# foe-scale.net
KiCad netlist of a schematic drawn in EAGLE
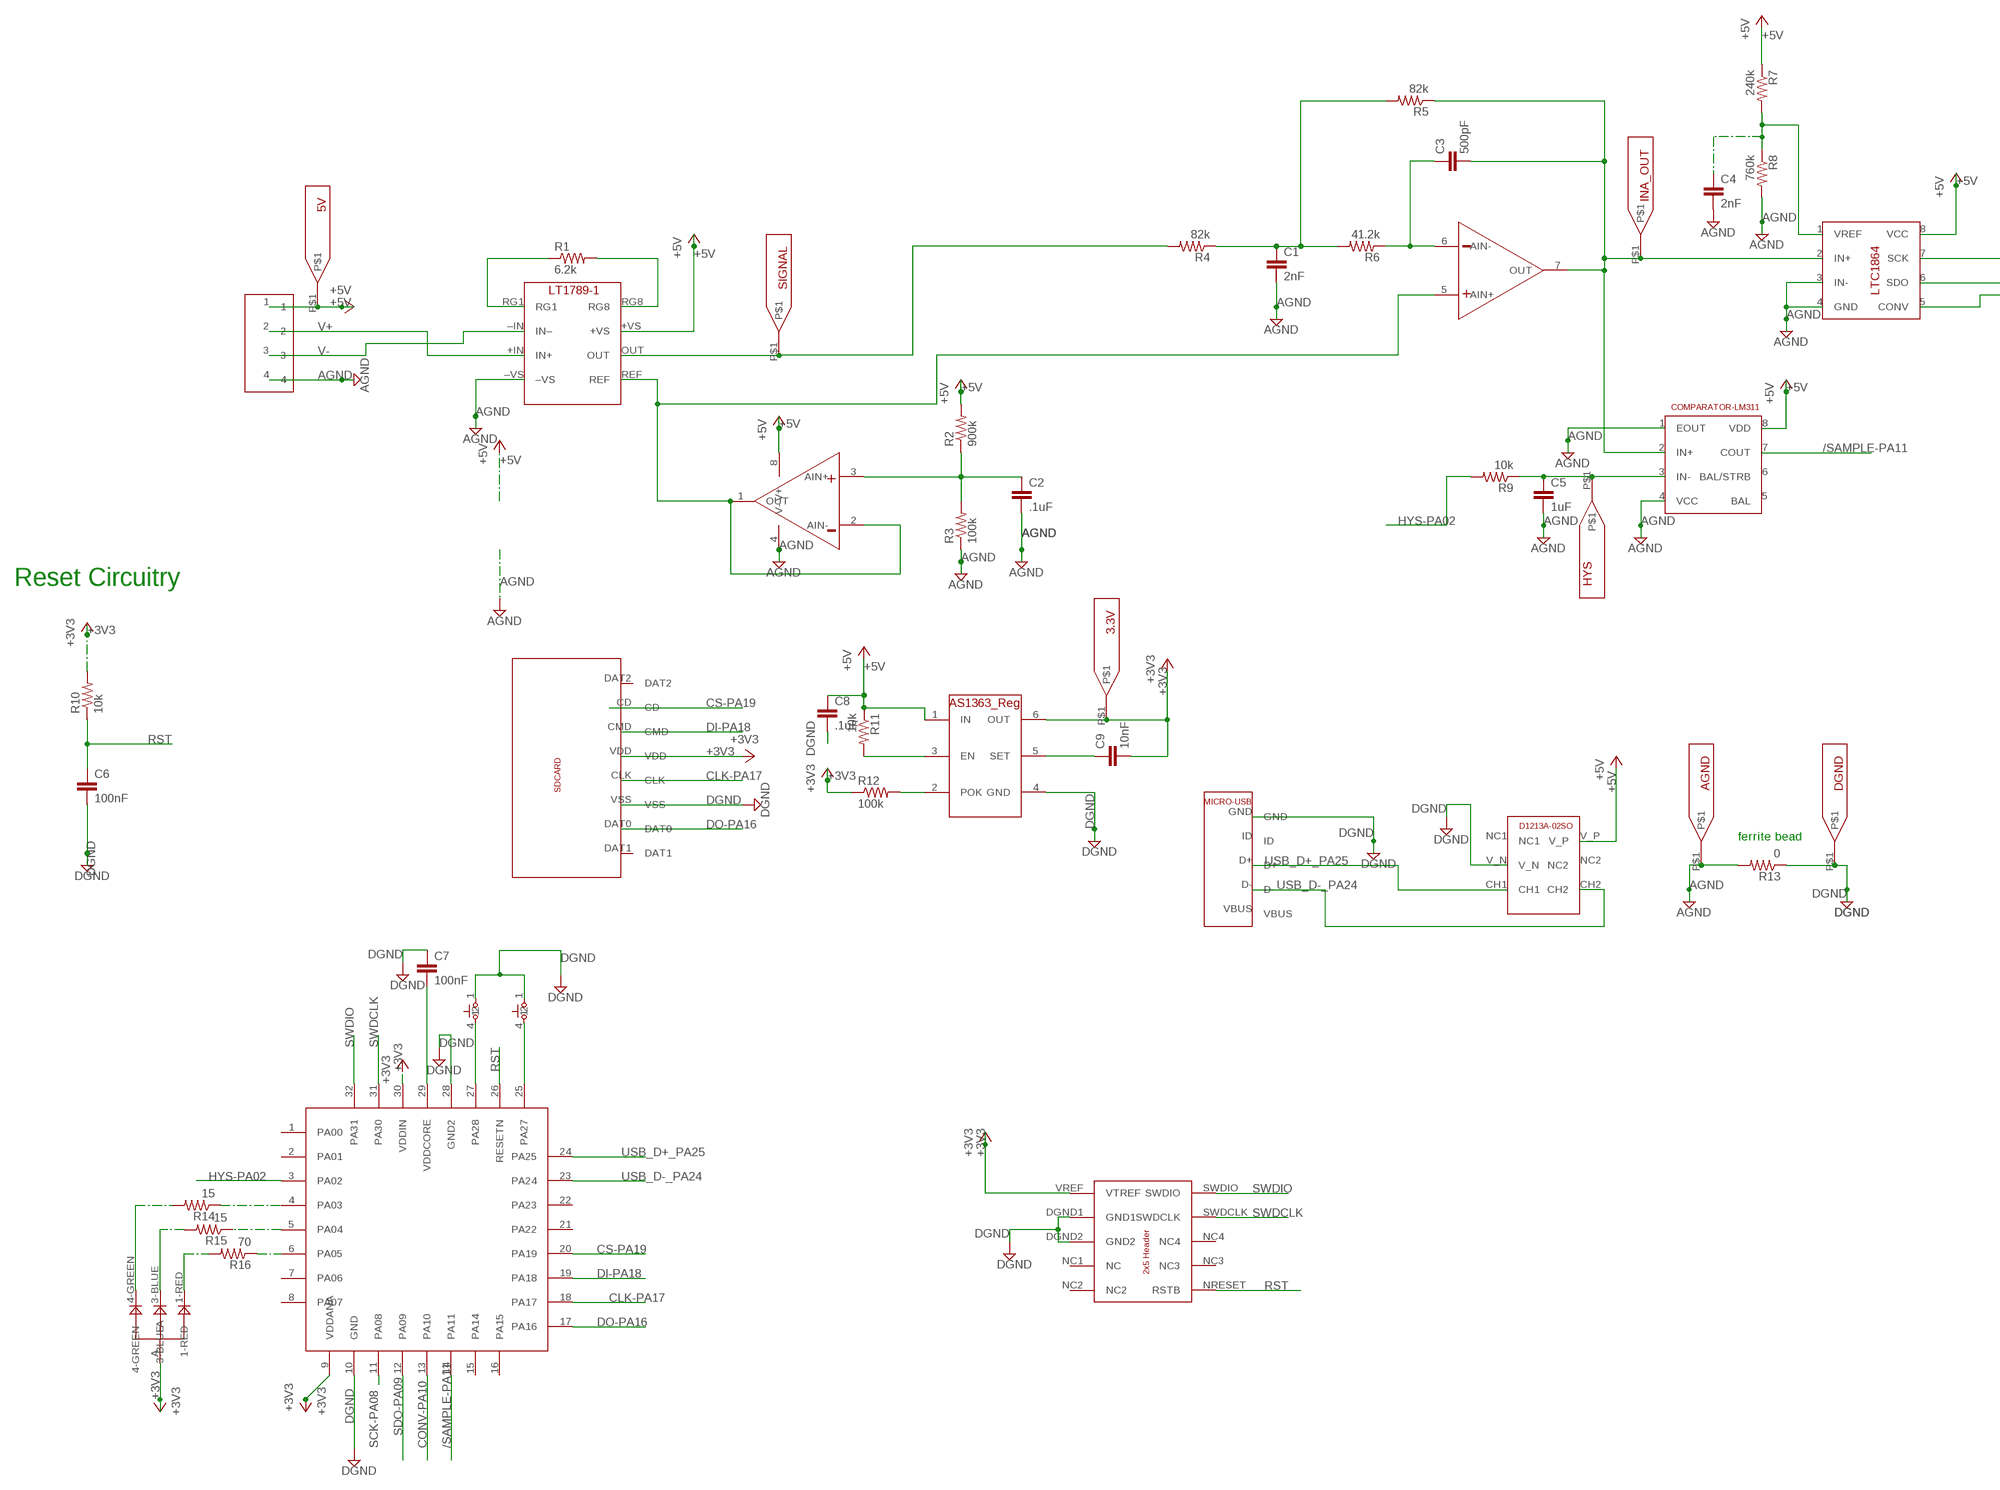
[diagram p0: schematic, sheet 1, part 1 of 2]
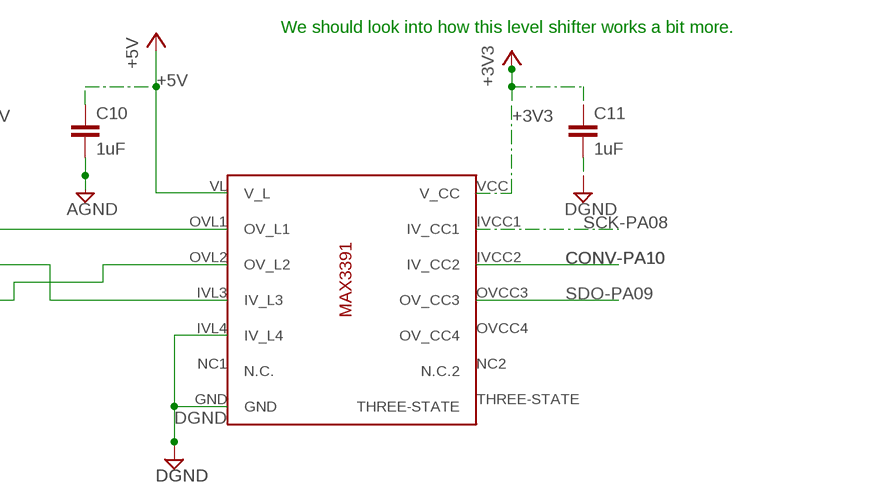
[diagram p1: schematic, sheet 1, part 2 of 2]

(export (version "E")
  (design (tool "Eeschema 10.0.6"))
  (components
    (comp (ref "3.3V")
      (value "TEST_POINT")
      (footprint "eagle-import:TEST_POINT")
      (libsource (lib "eagle-import") (part "TEST_POINT"))
    )
    (comp (ref "5V")
      (value "TEST_POINT")
      (footprint "eagle-import:TEST_POINT")
      (libsource (lib "eagle-import") (part "TEST_POINT"))
    )
    (comp (ref "AGND")
      (value "TEST_POINT")
      (footprint "eagle-import:TEST_POINT")
      (libsource (lib "eagle-import") (part "TEST_POINT"))
    )
    (comp (ref "AS1363")
      (value "3.3V_AS1363")
      (footprint "eagle-import:SOT23-6")
      (libsource (lib "eagle-import") (part "3.3V_AS1363"))
    )
    (comp (ref "C1")
      (value "2nF")
      (footprint "eagle-import:C0805K")
      (libsource (lib "eagle-import") (part "C-EUC0805K"))
    )
    (comp (ref "C2")
      (value ".1uF")
      (footprint "eagle-import:C0805K")
      (libsource (lib "eagle-import") (part "C-EUC0805K"))
    )
    (comp (ref "C3")
      (value "500pF")
      (footprint "eagle-import:C0805K")
      (libsource (lib "eagle-import") (part "C-EUC0805K"))
    )
    (comp (ref "C4")
      (value "2nF")
      (footprint "eagle-import:C0805K")
      (libsource (lib "eagle-import") (part "C-EUC0805K"))
    )
    (comp (ref "C5")
      (value "1uF")
      (footprint "eagle-import:C0805K")
      (libsource (lib "eagle-import") (part "C-EUC0805K"))
    )
    (comp (ref "C6")
      (value "100nF")
      (footprint "eagle-import:C0805K")
      (libsource (lib "eagle-import") (part "C-EUC0805K"))
    )
    (comp (ref "C7")
      (value "100nF")
      (footprint "eagle-import:C0805K")
      (libsource (lib "eagle-import") (part "C-EUC0805K"))
    )
    (comp (ref "C8")
      (value ".1uF")
      (footprint "eagle-import:C0805K")
      (libsource (lib "eagle-import") (part "C-EUC0805K"))
    )
    (comp (ref "C9")
      (value "10nF")
      (footprint "eagle-import:C0805K")
      (libsource (lib "eagle-import") (part "C-EUC0805K"))
    )
    (comp (ref "C10")
      (value "1uF")
      (footprint "eagle-import:C0805K")
      (libsource (lib "eagle-import") (part "C-EUC0805K"))
    )
    (comp (ref "C11")
      (value "1uF")
      (footprint "eagle-import:C0805K")
      (libsource (lib "eagle-import") (part "C-EUC0805K"))
    )
    (comp (ref "D1")
      (value "D1213A-DIODE-ARRAY")
      (footprint "eagle-import:SOT26-DIODE-ARRAY")
      (libsource (lib "eagle-import") (part "D1213A-DIODE-ARRAY"))
    )
    (comp (ref "DBG1")
      (value "DEBUGHEAD")
      (footprint "eagle-import:DEBUGHEAD")
      (libsource (lib "eagle-import") (part "DEBUGHEAD"))
    )
    (comp (ref "DGND")
      (value "TEST_POINT")
      (footprint "eagle-import:TEST_POINT")
      (libsource (lib "eagle-import") (part "TEST_POINT"))
    )
    (comp (ref "HYS")
      (value "TEST_POINT")
      (footprint "eagle-import:TEST_POINT")
      (libsource (lib "eagle-import") (part "TEST_POINT"))
    )
    (comp (ref "INA_OUT")
      (value "TEST_POINT")
      (footprint "eagle-import:TEST_POINT")
      (libsource (lib "eagle-import") (part "TEST_POINT"))
    )
    (comp (ref "R1")
      (value "6.2k")
      (footprint "eagle-import:R0805")
      (libsource (lib "eagle-import") (part "R-US_R0805"))
    )
    (comp (ref "R2")
      (value "900k")
      (footprint "eagle-import:R0805")
      (libsource (lib "eagle-import") (part "R-US_R0805"))
    )
    (comp (ref "R3")
      (value "100k")
      (footprint "eagle-import:R0805")
      (libsource (lib "eagle-import") (part "R-US_R0805"))
    )
    (comp (ref "R4")
      (value "82k")
      (footprint "eagle-import:R0805")
      (libsource (lib "eagle-import") (part "R-US_R0805"))
    )
    (comp (ref "R5")
      (value "82k")
      (footprint "eagle-import:R0805")
      (libsource (lib "eagle-import") (part "R-US_R0805"))
    )
    (comp (ref "R6")
      (value "41.2k")
      (footprint "eagle-import:R0805")
      (libsource (lib "eagle-import") (part "R-US_R0805"))
    )
    (comp (ref "R7")
      (value "240k")
      (footprint "eagle-import:R0805")
      (libsource (lib "eagle-import") (part "R-US_R0805"))
    )
    (comp (ref "R8")
      (value "760k")
      (footprint "eagle-import:R0805")
      (libsource (lib "eagle-import") (part "R-US_R0805"))
    )
    (comp (ref "R9")
      (value "10k")
      (footprint "eagle-import:R0805")
      (libsource (lib "eagle-import") (part "R-US_R0805"))
    )
    (comp (ref "R10")
      (value "10k")
      (footprint "eagle-import:R0805")
      (libsource (lib "eagle-import") (part "R-US_R0805"))
    )
    (comp (ref "R11")
      (value "10k")
      (footprint "eagle-import:R0805")
      (libsource (lib "eagle-import") (part "R-US_R0805"))
    )
    (comp (ref "R12")
      (value "100k")
      (footprint "eagle-import:R0805")
      (libsource (lib "eagle-import") (part "R-US_R0805"))
    )
    (comp (ref "R13")
      (value "0")
      (footprint "eagle-import:R0805")
      (libsource (lib "eagle-import") (part "R-US_R0805"))
    )
    (comp (ref "R14")
      (value "15")
      (footprint "eagle-import:R0805")
      (libsource (lib "eagle-import") (part "R-US_R0805"))
    )
    (comp (ref "R15")
      (value "15")
      (footprint "eagle-import:R0805")
      (libsource (lib "eagle-import") (part "R-US_R0805"))
    )
    (comp (ref "R16")
      (value "70")
      (footprint "eagle-import:R0805")
      (libsource (lib "eagle-import") (part "R-US_R0805"))
    )
    (comp (ref "SIGNAL")
      (value "TEST_POINT")
      (footprint "eagle-import:TEST_POINT")
      (libsource (lib "eagle-import") (part "TEST_POINT"))
    )
    (comp (ref "U$1")
      (value "1X04")
      (footprint "eagle-import:1X04")
      (libsource (lib "eagle-import") (part "1X04"))
    )
    (comp (ref "U$2")
      (value "LT1789-1-INSTR-AMP")
      (footprint "eagle-import:S8-LT1789-1")
      (libsource (lib "eagle-import") (part "LT1789-1-INSTR-AMP"))
    )
    (comp (ref "U$3")
      (value "LMC6482")
      (footprint "eagle-import:SOIC8")
      (libsource (lib "eagle-import") (part "LMC6482"))
    )
    (comp (ref "U$6")
      (value "ADC-LTC1864")
      (footprint "eagle-import:SOIC8")
      (libsource (lib "eagle-import") (part "ADC-LTC1864"))
    )
    (comp (ref "U$7")
      (value "LEVEL-SHIFTER")
      (footprint "eagle-import:TSSOP-14")
      (libsource (lib "eagle-import") (part "LEVEL-SHIFTER"))
    )
    (comp (ref "U$8")
      (value "SDCARD_JACK")
      (footprint "eagle-import:MICRO_SDCARD")
      (libsource (lib "eagle-import") (part "SDCARD_JACK"))
    )
    (comp (ref "U$10")
      (value "RGBLED")
      (footprint "eagle-import:RGBLED")
      (libsource (lib "eagle-import") (part "RGBLED"))
    )
    (comp (ref "U$11")
      (value "BUTTON_THRU")
      (footprint "eagle-import:PUSHBTN")
      (libsource (lib "eagle-import") (part "BUTTON_THRU"))
    )
    (comp (ref "U$12")
      (value "BUTTON_THRU")
      (footprint "eagle-import:PUSHBTN")
      (libsource (lib "eagle-import") (part "BUTTON_THRU"))
    )
    (comp (ref "U$13")
      (value "MICRO-USB-CONNECTOR")
      (footprint "eagle-import:MICRO-USB-CONNECTOR")
      (libsource (lib "eagle-import") (part "MICRO-USB-CONNECTOR"))
    )
    (comp (ref "U1")
      (value "LM311")
      (footprint "eagle-import:SOIC8")
      (libsource (lib "eagle-import") (part "LM311"))
    )
    (comp (ref "U2")
      (value "SAMD21E")
      (footprint "eagle-import:TQFP32-08")
      (libsource (lib "eagle-import") (part "SAMD21E"))
    )
  )
  (nets
    (net (code "1") (name "+3V3") (class "Default")
      (node (ref "3.3V") (pin "P$1") (pinfunction "P$1_P$1") (pintype "bidirectional"))
      (node (ref "AS1363") (pin "6") (pinfunction "OUT_6") (pintype "bidirectional"))
      (node (ref "C11") (pin "1") (pinfunction "1_1") (pintype "passive"))
      (node (ref "C9") (pin "2") (pinfunction "2_2") (pintype "passive"))
      (node (ref "DBG1") (pin "VREF") (pinfunction "VTREF_VREF") (pintype "bidirectional"))
      (node (ref "R10") (pin "2") (pinfunction "2_2") (pintype "passive"))
      (node (ref "R12") (pin "1") (pinfunction "1_1") (pintype "passive"))
      (node (ref "U$10") (pin "A") (pinfunction "A_A") (pintype "bidirectional"))
      (node (ref "U$7") (pin "VCC") (pinfunction "V_CC_VCC") (pintype "bidirectional"))
      (node (ref "U$8") (pin "VDD") (pinfunction "VDD_VDD") (pintype "bidirectional"))
      (node (ref "U2") (pin "30") (pinfunction "VDDIN_30") (pintype "bidirectional"))
      (node (ref "U2") (pin "9") (pinfunction "VDDANA_9") (pintype "bidirectional"))
    )
    (net (code "2") (name "+5V") (class "Default")
      (node (ref "5V") (pin "P$1") (pinfunction "P$1_P$1") (pintype "bidirectional"))
      (node (ref "AS1363") (pin "1") (pinfunction "IN_1") (pintype "bidirectional"))
      (node (ref "C10") (pin "1") (pinfunction "1_1") (pintype "passive"))
      (node (ref "C8") (pin "1") (pinfunction "1_1") (pintype "passive"))
      (node (ref "D1") (pin "V_P") (pinfunction "V_P_V_P") (pintype "bidirectional"))
      (node (ref "R11") (pin "1") (pinfunction "1_1") (pintype "passive"))
      (node (ref "R2") (pin "2") (pinfunction "2_2") (pintype "passive"))
      (node (ref "R7") (pin "1") (pinfunction "1_1") (pintype "passive"))
      (node (ref "U$1") (pin "1") (pinfunction "1_1") (pintype "bidirectional"))
      (node (ref "U$2") (pin "+VS") (pinfunction "+VS_+VS") (pintype "bidirectional"))
      (node (ref "U$3") (pin "8") (pinfunction "V+_8") (pintype "bidirectional"))
      (node (ref "U$6") (pin "8") (pinfunction "VCC_8") (pintype "bidirectional"))
      (node (ref "U$7") (pin "VL") (pinfunction "V_L_VL") (pintype "bidirectional"))
      (node (ref "U1") (pin "8") (pinfunction "VDD_8") (pintype "bidirectional"))
    )
    (net (code "3") (name "/CLK-PA17") (class "Default")
      (node (ref "U$8") (pin "CLK") (pinfunction "CLK_CLK") (pintype "bidirectional"))
      (node (ref "U2") (pin "18") (pinfunction "PA17_18") (pintype "bidirectional"))
    )
    (net (code "4") (name "/CONV-PA10") (class "Default")
      (node (ref "U$7") (pin "IVCC2") (pinfunction "IV_CC2_IVCC2") (pintype "bidirectional"))
      (node (ref "U2") (pin "13") (pinfunction "PA10_13") (pintype "bidirectional"))
    )
    (net (code "5") (name "/CS-PA19") (class "Default")
      (node (ref "U$8") (pin "CD") (pinfunction "CD_CD") (pintype "bidirectional"))
      (node (ref "U2") (pin "20") (pinfunction "PA19_20") (pintype "bidirectional"))
    )
    (net (code "6") (name "/DI-PA18") (class "Default")
      (node (ref "U$8") (pin "CMD") (pinfunction "CMD_CMD") (pintype "bidirectional"))
      (node (ref "U2") (pin "19") (pinfunction "PA18_19") (pintype "bidirectional"))
    )
    (net (code "7") (name "/DO-PA16") (class "Default")
      (node (ref "U$8") (pin "DAT0") (pinfunction "DAT0_DAT0") (pintype "bidirectional"))
      (node (ref "U2") (pin "17") (pinfunction "PA16_17") (pintype "bidirectional"))
    )
    (net (code "8") (name "/HYS-PA02") (class "Default")
      (node (ref "R9") (pin "2") (pinfunction "2_2") (pintype "passive"))
      (node (ref "U2") (pin "3") (pinfunction "PA02_3") (pintype "bidirectional"))
    )
    (net (code "9") (name "/RST") (class "Default")
      (node (ref "C6") (pin "1") (pinfunction "1_1") (pintype "passive"))
      (node (ref "DBG1") (pin "NRESET") (pinfunction "RSTB_NRESET") (pintype "bidirectional"))
      (node (ref "R10") (pin "1") (pinfunction "1_1") (pintype "passive"))
      (node (ref "U2") (pin "26") (pinfunction "RESETN_26") (pintype "bidirectional"))
    )
    (net (code "10") (name "/SCK-PA08") (class "Default")
      (node (ref "U$7") (pin "IVCC1") (pinfunction "IV_CC1_IVCC1") (pintype "bidirectional"))
      (node (ref "U2") (pin "11") (pinfunction "PA08_11") (pintype "bidirectional"))
    )
    (net (code "11") (name "/SDO-PA09") (class "Default")
      (node (ref "U$7") (pin "OVCC3") (pinfunction "OV_CC3_OVCC3") (pintype "bidirectional"))
      (node (ref "U2") (pin "12") (pinfunction "PA09_12") (pintype "bidirectional"))
    )
    (net (code "12") (name "/SWDCLK") (class "Default")
      (node (ref "DBG1") (pin "SWDCLK") (pinfunction "SWDCLK_SWDCLK") (pintype "bidirectional"))
      (node (ref "U2") (pin "31") (pinfunction "PA30_31") (pintype "bidirectional"))
    )
    (net (code "13") (name "/SWDIO") (class "Default")
      (node (ref "DBG1") (pin "SWDIO") (pinfunction "SWDIO_SWDIO") (pintype "bidirectional"))
      (node (ref "U2") (pin "32") (pinfunction "PA31_32") (pintype "bidirectional"))
    )
    (net (code "14") (name "/USB_D+_PA25") (class "Default")
      (node (ref "D1") (pin "CH1") (pinfunction "CH1_CH1") (pintype "bidirectional"))
      (node (ref "U$13") (pin "D+") (pinfunction "D+_D+") (pintype "bidirectional"))
      (node (ref "U2") (pin "24") (pinfunction "PA25_24") (pintype "bidirectional"))
    )
    (net (code "15") (name "/USB_D-_PA24") (class "Default")
      (node (ref "D1") (pin "CH2") (pinfunction "CH2_CH2") (pintype "bidirectional"))
      (node (ref "U$13") (pin "D-") (pinfunction "D-_D-") (pintype "bidirectional"))
      (node (ref "U2") (pin "23") (pinfunction "PA24_23") (pintype "bidirectional"))
    )
    (net (code "16") (name "/V+") (class "Default")
      (node (ref "U$1") (pin "2") (pinfunction "2_2") (pintype "bidirectional"))
      (node (ref "U$2") (pin "+IN") (pinfunction "IN+_+IN") (pintype "bidirectional"))
    )
    (net (code "17") (name "/V-") (class "Default")
      (node (ref "U$1") (pin "3") (pinfunction "3_3") (pintype "bidirectional"))
      (node (ref "U$2") (pin "–IN") (pinfunction "IN–_–IN") (pintype "bidirectional"))
    )
    (net (code "18") (name "/{slash}SAMPLE-PA11") (class "Default")
      (node (ref "U1") (pin "7") (pinfunction "COUT_7") (pintype "bidirectional"))
      (node (ref "U2") (pin "14") (pinfunction "PA11_14") (pintype "bidirectional"))
    )
    (net (code "19") (name "AGND") (class "Default")
      (node (ref "AGND") (pin "P$1") (pinfunction "P$1_P$1") (pintype "bidirectional"))
      (node (ref "C1") (pin "2") (pinfunction "2_2") (pintype "passive"))
      (node (ref "C10") (pin "2") (pinfunction "2_2") (pintype "passive"))
      (node (ref "C2") (pin "2") (pinfunction "2_2") (pintype "passive"))
      (node (ref "C4") (pin "2") (pinfunction "2_2") (pintype "passive"))
      (node (ref "C5") (pin "2") (pinfunction "2_2") (pintype "passive"))
      (node (ref "R13") (pin "2") (pinfunction "2_2") (pintype "passive"))
      (node (ref "R3") (pin "1") (pinfunction "1_1") (pintype "passive"))
      (node (ref "R8") (pin "2") (pinfunction "2_2") (pintype "passive"))
      (node (ref "U$1") (pin "4") (pinfunction "4_4") (pintype "bidirectional"))
      (node (ref "U$2") (pin "–VS") (pinfunction "–VS_–VS") (pintype "bidirectional"))
      (node (ref "U$3") (pin "4") (pinfunction "V-_4") (pintype "bidirectional"))
      (node (ref "U$6") (pin "3") (pinfunction "IN-_3") (pintype "bidirectional"))
      (node (ref "U$6") (pin "4") (pinfunction "GND_4") (pintype "bidirectional"))
      (node (ref "U1") (pin "1") (pinfunction "EOUT_1") (pintype "bidirectional"))
      (node (ref "U1") (pin "4") (pinfunction "VCC_4") (pintype "bidirectional"))
    )
    (net (code "20") (name "DGND") (class "Default")
      (node (ref "AS1363") (pin "4") (pinfunction "GND_4") (pintype "bidirectional"))
      (node (ref "C11") (pin "2") (pinfunction "2_2") (pintype "passive"))
      (node (ref "C6") (pin "2") (pinfunction "2_2") (pintype "passive"))
      (node (ref "C7") (pin "1") (pinfunction "1_1") (pintype "passive"))
      (node (ref "C8") (pin "2") (pinfunction "2_2") (pintype "passive"))
      (node (ref "D1") (pin "V_N") (pinfunction "V_N_V_N") (pintype "bidirectional"))
      (node (ref "DBG1") (pin "DGND1") (pinfunction "GND1_DGND1") (pintype "bidirectional"))
      (node (ref "DBG1") (pin "DGND2") (pinfunction "GND2_DGND2") (pintype "bidirectional"))
      (node (ref "DGND") (pin "P$1") (pinfunction "P$1_P$1") (pintype "bidirectional"))
      (node (ref "R13") (pin "1") (pinfunction "1_1") (pintype "passive"))
      (node (ref "U$11") (pin "1") (pinfunction "1_1") (pintype "bidirectional"))
      (node (ref "U$12") (pin "1") (pinfunction "1_1") (pintype "bidirectional"))
      (node (ref "U$13") (pin "GND") (pinfunction "GND_GND") (pintype "bidirectional"))
      (node (ref "U$7") (pin "GND") (pinfunction "GND_GND") (pintype "bidirectional"))
      (node (ref "U$7") (pin "IVL4") (pinfunction "IV_L4_IVL4") (pintype "bidirectional"))
      (node (ref "U$8") (pin "VSS") (pinfunction "VSS_VSS") (pintype "bidirectional"))
      (node (ref "U2") (pin "10") (pinfunction "GND_10") (pintype "bidirectional"))
      (node (ref "U2") (pin "28") (pinfunction "GND2_28") (pintype "bidirectional"))
    )
    (net (code "21") (name "Net-(AS1363-EN)") (class "Default")
      (node (ref "AS1363") (pin "3") (pinfunction "EN_3") (pintype "bidirectional"))
      (node (ref "R11") (pin "2") (pinfunction "2_2") (pintype "passive"))
    )
    (net (code "22") (name "Net-(AS1363-POK)") (class "Default")
      (node (ref "AS1363") (pin "2") (pinfunction "POK_2") (pintype "bidirectional"))
      (node (ref "R12") (pin "2") (pinfunction "2_2") (pintype "passive"))
    )
    (net (code "23") (name "Net-(AS1363-SET)") (class "Default")
      (node (ref "AS1363") (pin "5") (pinfunction "SET_5") (pintype "bidirectional"))
      (node (ref "C9") (pin "1") (pinfunction "1_1") (pintype "passive"))
    )
    (net (code "24") (name "Net-(C1-Pad1)") (class "Default")
      (node (ref "C1") (pin "1") (pinfunction "1_1") (pintype "passive"))
      (node (ref "R4") (pin "1") (pinfunction "1_1") (pintype "passive"))
      (node (ref "R5") (pin "2") (pinfunction "2_2") (pintype "passive"))
      (node (ref "R6") (pin "2") (pinfunction "2_2") (pintype "passive"))
    )
    (net (code "25") (name "Net-(R1-Pad1)") (class "Default")
      (node (ref "R1") (pin "1") (pinfunction "1_1") (pintype "passive"))
      (node (ref "U$2") (pin "RG1") (pinfunction "RG1_RG1") (pintype "bidirectional"))
    )
    (net (code "26") (name "Net-(R1-Pad2)") (class "Default")
      (node (ref "R1") (pin "2") (pinfunction "2_2") (pintype "passive"))
      (node (ref "U$2") (pin "RG8") (pinfunction "RG8_RG8") (pintype "bidirectional"))
    )
    (net (code "27") (name "Net-(R4-Pad2)") (class "Default")
      (node (ref "R4") (pin "2") (pinfunction "2_2") (pintype "passive"))
      (node (ref "SIGNAL") (pin "P$1") (pinfunction "P$1_P$1") (pintype "bidirectional"))
      (node (ref "U$2") (pin "OUT") (pinfunction "OUT_OUT") (pintype "bidirectional"))
    )
    (net (code "28") (name "Net-(R14-Pad2)") (class "Default")
      (node (ref "R14") (pin "2") (pinfunction "2_2") (pintype "passive"))
      (node (ref "U$10") (pin "4-GREEN") (pinfunction "4-GREEN_4-GREEN") (pintype "bidirectional"))
    )
    (net (code "29") (name "Net-(R15-Pad2)") (class "Default")
      (node (ref "R15") (pin "2") (pinfunction "2_2") (pintype "passive"))
      (node (ref "U$10") (pin "3-BLUE") (pinfunction "3-BLUE_3-BLUE") (pintype "bidirectional"))
    )
    (net (code "30") (name "Net-(R16-Pad2)") (class "Default")
      (node (ref "R16") (pin "2") (pinfunction "2_2") (pintype "passive"))
      (node (ref "U$10") (pin "1-RED") (pinfunction "1-RED_1-RED") (pintype "bidirectional"))
    )
    (net (code "31") (name "Net-(U$3A-AIN+)") (class "Default")
      (node (ref "C2") (pin "1") (pinfunction "1_1") (pintype "passive"))
      (node (ref "R2") (pin "1") (pinfunction "1_1") (pintype "passive"))
      (node (ref "R3") (pin "2") (pinfunction "2_2") (pintype "passive"))
      (node (ref "U$3") (pin "3") (pinfunction "AIN+_3") (pintype "bidirectional"))
    )
    (net (code "32") (name "Net-(U$3A-AIN-)") (class "Default")
      (node (ref "U$2") (pin "REF") (pinfunction "REF_REF") (pintype "bidirectional"))
      (node (ref "U$3") (pin "1") (pinfunction "OUT_1") (pintype "bidirectional"))
      (node (ref "U$3") (pin "2") (pinfunction "AIN-_2") (pintype "bidirectional"))
      (node (ref "U$3") (pin "5") (pinfunction "AIN+_5") (pintype "bidirectional"))
    )
    (net (code "33") (name "Net-(U$3B-AIN-)") (class "Default")
      (node (ref "C3") (pin "1") (pinfunction "1_1") (pintype "passive"))
      (node (ref "R6") (pin "1") (pinfunction "1_1") (pintype "passive"))
      (node (ref "U$3") (pin "6") (pinfunction "AIN-_6") (pintype "bidirectional"))
    )
    (net (code "34") (name "Net-(U$3B-OUT)") (class "Default")
      (node (ref "C3") (pin "2") (pinfunction "2_2") (pintype "passive"))
      (node (ref "INA_OUT") (pin "P$1") (pinfunction "P$1_P$1") (pintype "bidirectional"))
      (node (ref "R5") (pin "1") (pinfunction "1_1") (pintype "passive"))
      (node (ref "U$3") (pin "7") (pinfunction "OUT_7") (pintype "bidirectional"))
      (node (ref "U$6") (pin "2") (pinfunction "IN+_2") (pintype "bidirectional"))
      (node (ref "U1") (pin "2") (pinfunction "IN+_2") (pintype "bidirectional"))
    )
    (net (code "35") (name "Net-(U$6-CONV)") (class "Default")
      (node (ref "U$6") (pin "5") (pinfunction "CONV_5") (pintype "bidirectional"))
      (node (ref "U$7") (pin "OVL2") (pinfunction "OV_L2_OVL2") (pintype "bidirectional"))
    )
    (net (code "36") (name "Net-(U$6-SCK)") (class "Default")
      (node (ref "U$6") (pin "7") (pinfunction "SCK_7") (pintype "bidirectional"))
      (node (ref "U$7") (pin "OVL1") (pinfunction "OV_L1_OVL1") (pintype "bidirectional"))
    )
    (net (code "37") (name "Net-(U$6-SDO)") (class "Default")
      (node (ref "U$6") (pin "6") (pinfunction "SDO_6") (pintype "bidirectional"))
      (node (ref "U$7") (pin "IVL3") (pinfunction "IV_L3_IVL3") (pintype "bidirectional"))
    )
    (net (code "38") (name "Net-(U$6-VREF)") (class "Default")
      (node (ref "C4") (pin "1") (pinfunction "1_1") (pintype "passive"))
      (node (ref "R7") (pin "2") (pinfunction "2_2") (pintype "passive"))
      (node (ref "R8") (pin "1") (pinfunction "1_1") (pintype "passive"))
      (node (ref "U$6") (pin "1") (pinfunction "VREF_1") (pintype "bidirectional"))
    )
    (net (code "39") (name "Net-(U$11-2)") (class "Default")
      (node (ref "U$11") (pin "4") (pinfunction "2_4") (pintype "bidirectional"))
      (node (ref "U2") (pin "25") (pinfunction "PA27_25") (pintype "bidirectional"))
    )
    (net (code "40") (name "Net-(U$12-2)") (class "Default")
      (node (ref "U$12") (pin "4") (pinfunction "2_4") (pintype "bidirectional"))
      (node (ref "U2") (pin "27") (pinfunction "PA28_27") (pintype "bidirectional"))
    )
    (net (code "41") (name "Net-(U1-IN-)") (class "Default")
      (node (ref "C5") (pin "1") (pinfunction "1_1") (pintype "passive"))
      (node (ref "HYS") (pin "P$1") (pinfunction "P$1_P$1") (pintype "bidirectional"))
      (node (ref "R9") (pin "1") (pinfunction "1_1") (pintype "passive"))
      (node (ref "U1") (pin "3") (pinfunction "IN-_3") (pintype "bidirectional"))
    )
    (net (code "42") (name "Net-(U2-PA03)") (class "Default")
      (node (ref "R14") (pin "1") (pinfunction "1_1") (pintype "passive"))
      (node (ref "U2") (pin "4") (pinfunction "PA03_4") (pintype "bidirectional"))
    )
    (net (code "43") (name "Net-(U2-PA04)") (class "Default")
      (node (ref "R15") (pin "1") (pinfunction "1_1") (pintype "passive"))
      (node (ref "U2") (pin "5") (pinfunction "PA04_5") (pintype "bidirectional"))
    )
    (net (code "44") (name "Net-(U2-PA05)") (class "Default")
      (node (ref "R16") (pin "1") (pinfunction "1_1") (pintype "passive"))
      (node (ref "U2") (pin "6") (pinfunction "PA05_6") (pintype "bidirectional"))
    )
    (net (code "45") (name "Net-(U2-VDDCORE)") (class "Default")
      (node (ref "C7") (pin "2") (pinfunction "2_2") (pintype "passive"))
      (node (ref "U2") (pin "29") (pinfunction "VDDCORE_29") (pintype "bidirectional"))
    )
    (net (code "46") (name "unconnected-(D1-PadNC1)") (class "Default")
      (node (ref "D1") (pin "NC1") (pinfunction "NC1_NC1") (pintype "bidirectional"))
    )
    (net (code "47") (name "unconnected-(D1-PadNC2)") (class "Default")
      (node (ref "D1") (pin "NC2") (pinfunction "NC2_NC2") (pintype "bidirectional"))
    )
    (net (code "48") (name "unconnected-(DBG1-NC-PadNC1)") (class "Default")
      (node (ref "DBG1") (pin "NC1") (pinfunction "NC_NC1") (pintype "bidirectional"))
    )
    (net (code "49") (name "unconnected-(DBG1-PadNC2)") (class "Default")
      (node (ref "DBG1") (pin "NC2") (pinfunction "NC2_NC2") (pintype "bidirectional"))
    )
    (net (code "50") (name "unconnected-(DBG1-PadNC3)") (class "Default")
      (node (ref "DBG1") (pin "NC3") (pinfunction "NC3_NC3") (pintype "bidirectional"))
    )
    (net (code "51") (name "unconnected-(DBG1-PadNC4)") (class "Default")
      (node (ref "DBG1") (pin "NC4") (pinfunction "NC4_NC4") (pintype "bidirectional"))
    )
    (net (code "52") (name "unconnected-(U$7-N.C.-PadNC1)") (class "Default")
      (node (ref "U$7") (pin "NC1") (pinfunction "N.C._NC1") (pintype "bidirectional"))
    )
    (net (code "53") (name "unconnected-(U$7-N.C.2-PadNC2)") (class "Default")
      (node (ref "U$7") (pin "NC2") (pinfunction "N.C.2_NC2") (pintype "bidirectional"))
    )
    (net (code "54") (name "unconnected-(U$7-OV_CC4-PadOVCC4)") (class "Default")
      (node (ref "U$7") (pin "OVCC4") (pinfunction "OV_CC4_OVCC4") (pintype "bidirectional"))
    )
    (net (code "55") (name "unconnected-(U$7-PadTHREE-STATE)") (class "Default")
      (node (ref "U$7") (pin "THREE-STATE") (pinfunction "THREE-STATE_THREE-STATE") (pintype "bidirectional"))
    )
    (net (code "56") (name "unconnected-(U$8-PadDAT1)") (class "Default")
      (node (ref "U$8") (pin "DAT1") (pinfunction "DAT1_DAT1") (pintype "bidirectional"))
    )
    (net (code "57") (name "unconnected-(U$8-PadDAT2)") (class "Default")
      (node (ref "U$8") (pin "DAT2") (pinfunction "DAT2_DAT2") (pintype "bidirectional"))
    )
    (net (code "58") (name "unconnected-(U$13-PadID)") (class "Default")
      (node (ref "U$13") (pin "ID") (pinfunction "ID_ID") (pintype "bidirectional"))
    )
    (net (code "59") (name "unconnected-(U$13-PadVBUS)") (class "Default")
      (node (ref "U$13") (pin "VBUS") (pinfunction "VBUS_VBUS") (pintype "bidirectional"))
    )
    (net (code "60") (name "unconnected-(U1-BAL-Pad5)") (class "Default")
      (node (ref "U1") (pin "5") (pinfunction "BAL_5") (pintype "bidirectional"))
    )
    (net (code "61") (name "unconnected-(U1-BAL{slash}STRB-Pad6)") (class "Default")
      (node (ref "U1") (pin "6") (pinfunction "BAL/STRB_6") (pintype "bidirectional"))
    )
    (net (code "62") (name "unconnected-(U2-PA00-Pad1)") (class "Default")
      (node (ref "U2") (pin "1") (pinfunction "PA00_1") (pintype "bidirectional"))
    )
    (net (code "63") (name "unconnected-(U2-PA01-Pad2)") (class "Default")
      (node (ref "U2") (pin "2") (pinfunction "PA01_2") (pintype "bidirectional"))
    )
    (net (code "64") (name "unconnected-(U2-PA06-Pad7)") (class "Default")
      (node (ref "U2") (pin "7") (pinfunction "PA06_7") (pintype "bidirectional"))
    )
    (net (code "65") (name "unconnected-(U2-PA07-Pad8)") (class "Default")
      (node (ref "U2") (pin "8") (pinfunction "PA07_8") (pintype "bidirectional"))
    )
    (net (code "66") (name "unconnected-(U2-PA14-Pad15)") (class "Default")
      (node (ref "U2") (pin "15") (pinfunction "PA14_15") (pintype "bidirectional"))
    )
    (net (code "67") (name "unconnected-(U2-PA15-Pad16)") (class "Default")
      (node (ref "U2") (pin "16") (pinfunction "PA15_16") (pintype "bidirectional"))
    )
    (net (code "68") (name "unconnected-(U2-PA22-Pad21)") (class "Default")
      (node (ref "U2") (pin "21") (pinfunction "PA22_21") (pintype "bidirectional"))
    )
    (net (code "69") (name "unconnected-(U2-PA23-Pad22)") (class "Default")
      (node (ref "U2") (pin "22") (pinfunction "PA23_22") (pintype "bidirectional"))
    )
  )
)
